# shift_relays.net
KiCad netlist of a schematic drawn in Altium Designer
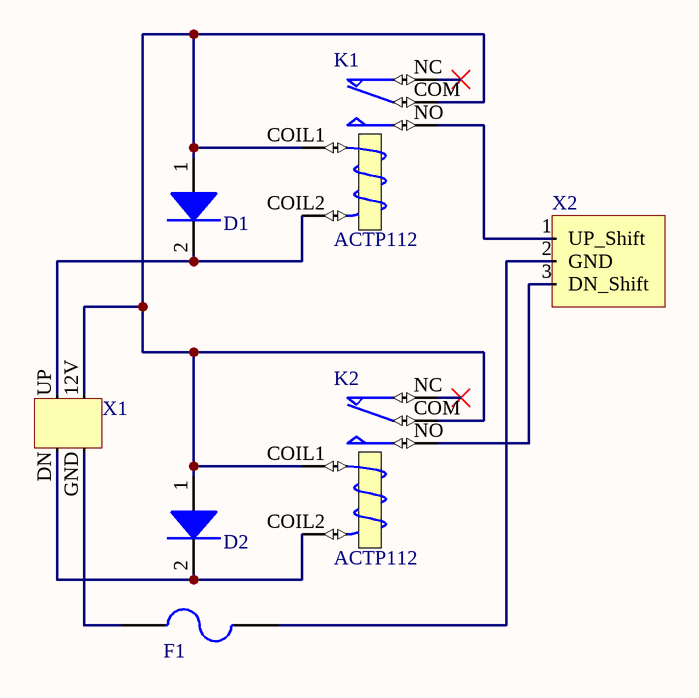
[diagram p0: shift_relays.SchDoc]

(export (version "E")
  (design (tool "Eeschema 10.0.6"))
  (components
    (comp (ref "D1")
      (value "*")
      (footprint "DO214AA_ SD560BTR")
      (description "Diode Standard 600V 5A Surface Mount SMB")
      (libsource (lib "altlib") (part "DIODE"))
    )
    (comp (ref "D2")
      (value "*")
      (footprint "DO214AA_ SD560BTR")
      (description "Diode Standard 600V 5A Surface Mount SMB")
      (libsource (lib "altlib") (part "DIODE"))
    )
    (comp (ref "F1")
      (value "Fuse")
      (footprint "3568-MiniFuseHolder")
      (libsource (lib "altlib") (part "Fuse"))
    )
    (comp (ref "K1")
      (value "ACTP112")
      (footprint "ACTP112")
      (fields
        (field (name "VOLTAGE") "12")
        (field (name "PUBLISHER") "Altium Limited")
        (field (name "CREATEDBY") "Kevin")
      )
      (libsource (lib "altlib") (part "ACTP112"))
    )
    (comp (ref "K2")
      (value "ACTP112")
      (footprint "ACTP112")
      (fields
        (field (name "VOLTAGE") "12")
        (field (name "PUBLISHER") "Altium Limited")
        (field (name "CREATEDBY") "Kevin")
      )
      (libsource (lib "altlib") (part "ACTP112"))
    )
    (comp (ref "X1")
      (value "*")
      (footprint "DTF13-4P")
      (description "DTF13-4P")
      (libsource (lib "altlib") (part "CONN 4POS"))
    )
    (comp (ref "X2")
      (value "~")
      (footprint "CONN_Shift")
      (description "Connector for Shift Relays")
      (fields (field (name "CREATEDBY") "Patrick"))
      (libsource (lib "altlib") (part "CONN Shift"))
    )
  )
  (nets
    (net (code "1") (name "Net-(D1-A)") (class "Default")
      (node (ref "D1") (pin "1") (pinfunction "A_1") (pintype "passive"))
      (node (ref "D2") (pin "1") (pinfunction "A_1") (pintype "passive"))
      (node (ref "K1") (pin "COIL1") (pinfunction "T1_COIL1") (pintype "bidirectional"))
      (node (ref "K1") (pin "COM") (pinfunction "COM_COM") (pintype "bidirectional"))
      (node (ref "K2") (pin "COIL1") (pinfunction "T1_COIL1") (pintype "bidirectional"))
      (node (ref "K2") (pin "COM") (pinfunction "COM_COM") (pintype "bidirectional"))
      (node (ref "X1") (pin "12V") (pintype "output"))
    )
    (net (code "2") (name "Net-(D1-K)") (class "Default")
      (node (ref "D1") (pin "2") (pinfunction "K_2") (pintype "passive"))
      (node (ref "K1") (pin "COIL2") (pinfunction "T2_COIL2") (pintype "bidirectional"))
      (node (ref "X1") (pin "UP") (pintype "output"))
    )
    (net (code "3") (name "Net-(D2-K)") (class "Default")
      (node (ref "D2") (pin "2") (pinfunction "K_2") (pintype "passive"))
      (node (ref "K2") (pin "COIL2") (pinfunction "T2_COIL2") (pintype "bidirectional"))
      (node (ref "X1") (pin "DN") (pintype "output"))
    )
    (net (code "4") (name "Net-(F1-Pad1)") (class "Default")
      (node (ref "F1") (pin "1") (pinfunction "1_1") (pintype "passive"))
      (node (ref "X1") (pin "GND") (pintype "output"))
    )
    (net (code "5") (name "Net-(X2-DN_Shift)") (class "Default")
      (node (ref "K2") (pin "NO") (pinfunction "NO_NO") (pintype "bidirectional"))
      (node (ref "X2") (pin "3") (pinfunction "DN_Shift_3") (pintype "input"))
    )
    (net (code "6") (name "Net-(X2-GND)") (class "Default")
      (node (ref "F1") (pin "2") (pinfunction "2_2") (pintype "passive"))
      (node (ref "X2") (pin "2") (pinfunction "GND_2") (pintype "input"))
    )
    (net (code "7") (name "Net-(X2-UP_Shift)") (class "Default")
      (node (ref "K1") (pin "NO") (pinfunction "NO_NO") (pintype "bidirectional"))
      (node (ref "X2") (pin "1") (pinfunction "UP_Shift_1") (pintype "input"))
    )
    (net (code "8") (name "unconnected-(K1-PadNC)") (class "Default")
      (node (ref "K1") (pin "NC") (pinfunction "NC_NC") (pintype "bidirectional+no_connect"))
    )
    (net (code "9") (name "unconnected-(K2-PadNC)") (class "Default")
      (node (ref "K2") (pin "NC") (pinfunction "NC_NC") (pintype "bidirectional+no_connect"))
    )
  )
)
